# Transmitter.net
KiCad netlist of a schematic drawn in EAGLE
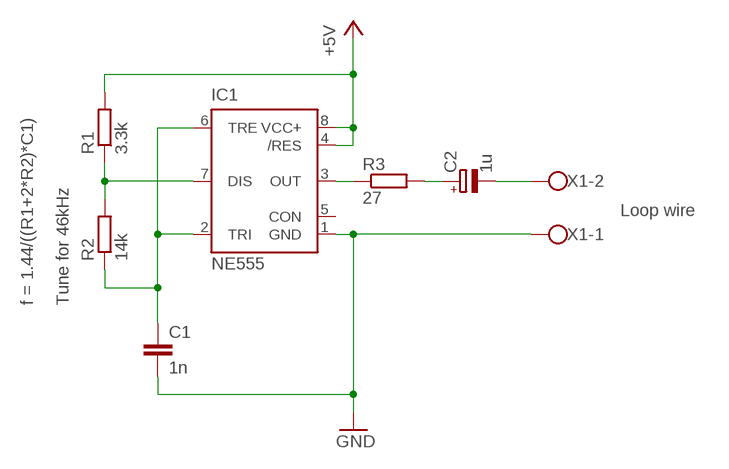
[diagram p0: schematic, sheet 1]

(export (version "E")
  (design (tool "Eeschema 10.0.6"))
  (components
    (comp (ref "C1")
      (value "1n")
      (footprint "eagle-import:C075-032X103")
      (libsource (lib "eagle-import") (part "C-EU075-032X103"))
    )
    (comp (ref "C2")
      (value "1u")
      (footprint "eagle-import:E2,5-5")
      (libsource (lib "eagle-import") (part "CPOL-EUE2.5-5"))
    )
    (comp (ref "IC1")
      (value "NE555")
      (footprint "eagle-import:DIL-08")
      (fields (field (name "MF") "Arrow Electronics") (field (name "MPN") "NE555N"))
      (libsource (lib "eagle-import") (part "NE555"))
    )
    (comp (ref "R1")
      (value "3.3k")
      (footprint "eagle-import:0204V")
      (libsource (lib "eagle-import") (part "R-EU_0204/2V"))
    )
    (comp (ref "R2")
      (value "14k")
      (footprint "eagle-import:0204V")
      (libsource (lib "eagle-import") (part "R-EU_0204/2V"))
    )
    (comp (ref "R3")
      (value "27")
      (footprint "eagle-import:0411_12")
      (libsource (lib "eagle-import") (part "R-EU_0411/12"))
    )
    (comp (ref "X1")
      (value "W237-102")
      (footprint "eagle-import:W237-102")
      (fields (field (name "MPN") "237-102"))
      (libsource (lib "eagle-import") (part "W237-102"))
    )
  )
  (nets
    (net (code "1") (name "+5V") (class "Default")
      (node (ref "IC1") (pin "4") (pinfunction "/RES_4") (pintype "input"))
      (node (ref "IC1") (pin "8") (pinfunction "VCC+_8") (pintype "power_in"))
      (node (ref "R1") (pin "2") (pinfunction "2_2") (pintype "passive"))
    )
    (net (code "2") (name "GND") (class "Default")
      (node (ref "C1") (pin "2") (pinfunction "2_2") (pintype "passive"))
      (node (ref "IC1") (pin "1") (pinfunction "GND_1") (pintype "power_in"))
      (node (ref "X1") (pin "1") (pinfunction "KL_1") (pintype "passive"))
    )
    (net (code "3") (name "Net-(C2-Pad+)") (class "Default")
      (node (ref "C2") (pin "+") (pinfunction "+_+") (pintype "passive"))
      (node (ref "R3") (pin "2") (pinfunction "2_2") (pintype "passive"))
    )
    (net (code "4") (name "Net-(IC1-DIS)") (class "Default")
      (node (ref "IC1") (pin "7") (pinfunction "DIS_7") (pintype "input"))
      (node (ref "R1") (pin "1") (pinfunction "1_1") (pintype "passive"))
      (node (ref "R2") (pin "2") (pinfunction "2_2") (pintype "passive"))
    )
    (net (code "5") (name "Net-(IC1-OUT)") (class "Default")
      (node (ref "IC1") (pin "3") (pinfunction "OUT_3") (pintype "output"))
      (node (ref "R3") (pin "1") (pinfunction "1_1") (pintype "passive"))
    )
    (net (code "6") (name "Net-(IC1-TRE)") (class "Default")
      (node (ref "C1") (pin "1") (pinfunction "1_1") (pintype "passive"))
      (node (ref "IC1") (pin "2") (pinfunction "TRI_2") (pintype "input"))
      (node (ref "IC1") (pin "6") (pinfunction "TRE_6") (pintype "input"))
      (node (ref "R2") (pin "1") (pinfunction "1_1") (pintype "passive"))
    )
    (net (code "7") (name "Net-(X1B-KL)") (class "Default")
      (node (ref "C2") (pin "-") (pinfunction "-_-") (pintype "passive"))
      (node (ref "X1") (pin "2") (pinfunction "KL_2") (pintype "passive"))
    )
    (net (code "8") (name "unconnected-(IC1-CON-Pad5)") (class "Default")
      (node (ref "IC1") (pin "5") (pinfunction "CON_5") (pintype "input"))
    )
  )
)
